# M500X.net
KiCad netlist of a schematic drawn in EAGLE
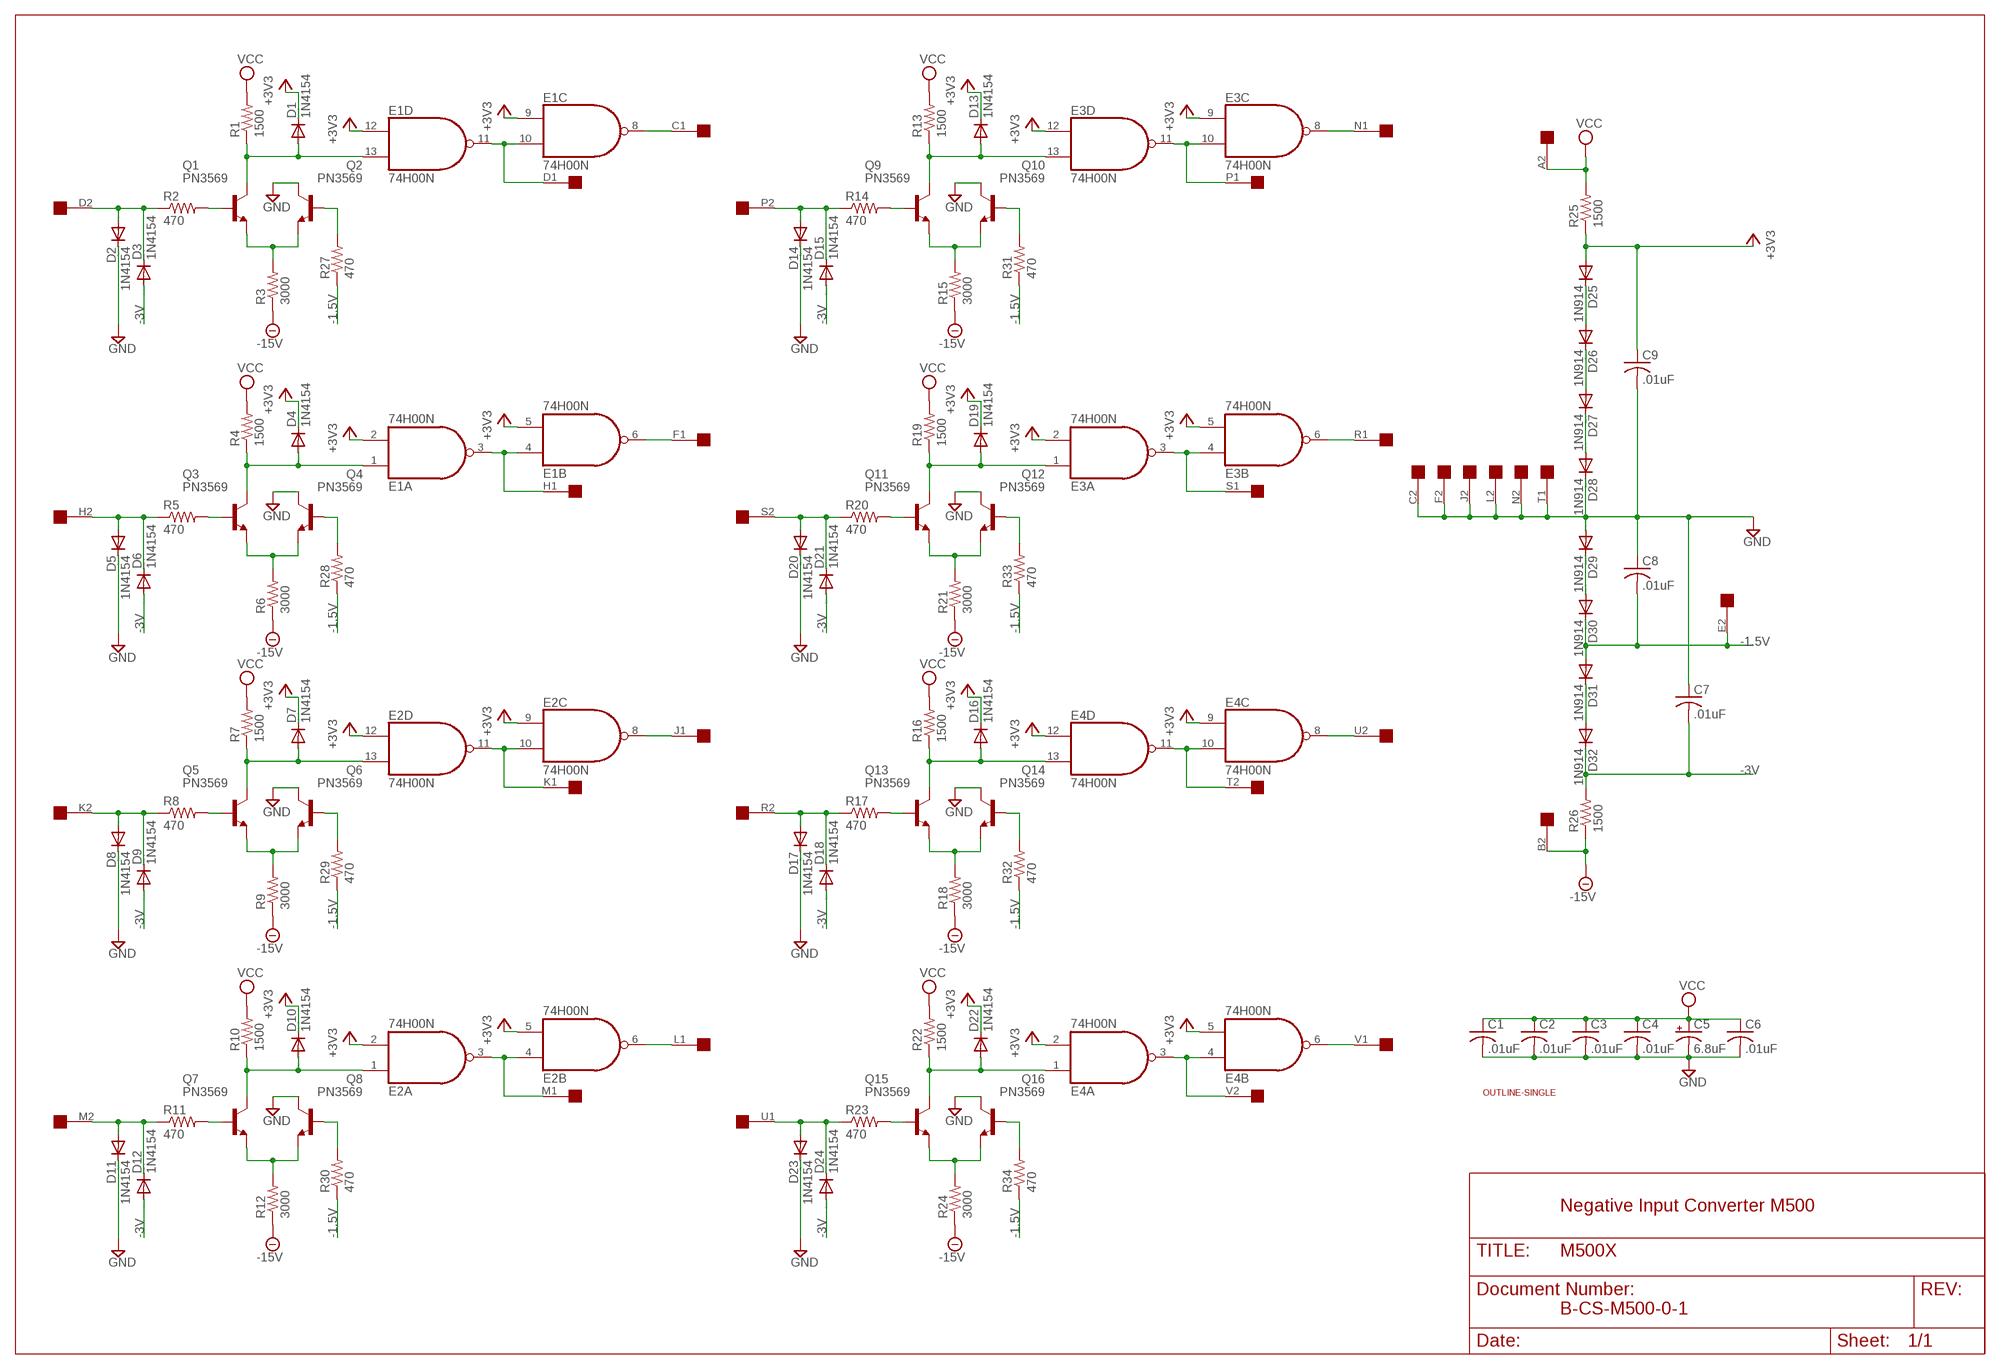
[diagram p0: schematic, sheet 1]

(export (version "E")
  (design (tool "Eeschema 10.0.6"))
  (components
    (comp (ref "C1")
      (value ".01uF")
      (footprint "eagle-import:C050-025X075")
      (libsource (lib "eagle-import") (part "C-US050-025X075"))
    )
    (comp (ref "C2")
      (value ".01uF")
      (footprint "eagle-import:C050-025X075")
      (libsource (lib "eagle-import") (part "C-US050-025X075"))
    )
    (comp (ref "C3")
      (value ".01uF")
      (footprint "eagle-import:C050-025X075")
      (libsource (lib "eagle-import") (part "C-US050-025X075"))
    )
    (comp (ref "C4")
      (value ".01uF")
      (footprint "eagle-import:C050-025X075")
      (libsource (lib "eagle-import") (part "C-US050-025X075"))
    )
    (comp (ref "C5")
      (value "6.8uF")
      (footprint "eagle-import:E12-8")
      (libsource (lib "eagle-import") (part "CPOL-USE20-8AXIAL"))
    )
    (comp (ref "C6")
      (value ".01uF")
      (footprint "eagle-import:C050-025X075")
      (libsource (lib "eagle-import") (part "C-US050-025X075"))
    )
    (comp (ref "C7")
      (value ".01uF")
      (footprint "eagle-import:C050-025X075")
      (libsource (lib "eagle-import") (part "C-US050-025X075"))
    )
    (comp (ref "C8")
      (value ".01uF")
      (footprint "eagle-import:C050-025X075")
      (libsource (lib "eagle-import") (part "C-US050-025X075"))
    )
    (comp (ref "C9")
      (value ".01uF")
      (footprint "eagle-import:C050-025X075")
      (libsource (lib "eagle-import") (part "C-US050-025X075"))
    )
    (comp (ref "D1")
      (value "1N4154")
      (footprint "eagle-import:DO35-10")
      (libsource (lib "eagle-import") (part "1N4148DO35-10"))
    )
    (comp (ref "D2")
      (value "1N4154")
      (footprint "eagle-import:DO35-10")
      (libsource (lib "eagle-import") (part "1N4148DO35-10"))
    )
    (comp (ref "D3")
      (value "1N4154")
      (footprint "eagle-import:DO35-10")
      (libsource (lib "eagle-import") (part "1N4148DO35-10"))
    )
    (comp (ref "D4")
      (value "1N4154")
      (footprint "eagle-import:DO35-10")
      (libsource (lib "eagle-import") (part "1N4148DO35-10"))
    )
    (comp (ref "D5")
      (value "1N4154")
      (footprint "eagle-import:DO35-10")
      (libsource (lib "eagle-import") (part "1N4148DO35-10"))
    )
    (comp (ref "D6")
      (value "1N4154")
      (footprint "eagle-import:DO35-10")
      (libsource (lib "eagle-import") (part "1N4148DO35-10"))
    )
    (comp (ref "D7")
      (value "1N4154")
      (footprint "eagle-import:DO35-10")
      (libsource (lib "eagle-import") (part "1N4148DO35-10"))
    )
    (comp (ref "D8")
      (value "1N4154")
      (footprint "eagle-import:DO35-10")
      (libsource (lib "eagle-import") (part "1N4148DO35-10"))
    )
    (comp (ref "D9")
      (value "1N4154")
      (footprint "eagle-import:DO35-10")
      (libsource (lib "eagle-import") (part "1N4148DO35-10"))
    )
    (comp (ref "D10")
      (value "1N4154")
      (footprint "eagle-import:DO35-10")
      (libsource (lib "eagle-import") (part "1N4148DO35-10"))
    )
    (comp (ref "D11")
      (value "1N4154")
      (footprint "eagle-import:DO35-10")
      (libsource (lib "eagle-import") (part "1N4148DO35-10"))
    )
    (comp (ref "D12")
      (value "1N4154")
      (footprint "eagle-import:DO35-10")
      (libsource (lib "eagle-import") (part "1N4148DO35-10"))
    )
    (comp (ref "D13")
      (value "1N4154")
      (footprint "eagle-import:DO35-10")
      (libsource (lib "eagle-import") (part "1N4148DO35-10"))
    )
    (comp (ref "D14")
      (value "1N4154")
      (footprint "eagle-import:DO35-10")
      (libsource (lib "eagle-import") (part "1N4148DO35-10"))
    )
    (comp (ref "D15")
      (value "1N4154")
      (footprint "eagle-import:DO35-10")
      (libsource (lib "eagle-import") (part "1N4148DO35-10"))
    )
    (comp (ref "D16")
      (value "1N4154")
      (footprint "eagle-import:DO35-10")
      (libsource (lib "eagle-import") (part "1N4148DO35-10"))
    )
    (comp (ref "D17")
      (value "1N4154")
      (footprint "eagle-import:DO35-10")
      (libsource (lib "eagle-import") (part "1N4148DO35-10"))
    )
    (comp (ref "D18")
      (value "1N4154")
      (footprint "eagle-import:DO35-10")
      (libsource (lib "eagle-import") (part "1N4148DO35-10"))
    )
    (comp (ref "D19")
      (value "1N4154")
      (footprint "eagle-import:DO35-10")
      (libsource (lib "eagle-import") (part "1N4148DO35-10"))
    )
    (comp (ref "D20")
      (value "1N4154")
      (footprint "eagle-import:DO35-10")
      (libsource (lib "eagle-import") (part "1N4148DO35-10"))
    )
    (comp (ref "D21")
      (value "1N4154")
      (footprint "eagle-import:DO35-10")
      (libsource (lib "eagle-import") (part "1N4148DO35-10"))
    )
    (comp (ref "D22")
      (value "1N4154")
      (footprint "eagle-import:DO35-10")
      (libsource (lib "eagle-import") (part "1N4148DO35-10"))
    )
    (comp (ref "D23")
      (value "1N4154")
      (footprint "eagle-import:DO35-10")
      (libsource (lib "eagle-import") (part "1N4148DO35-10"))
    )
    (comp (ref "D24")
      (value "1N4154")
      (footprint "eagle-import:DO35-10")
      (libsource (lib "eagle-import") (part "1N4148DO35-10"))
    )
    (comp (ref "D25")
      (value "1N914")
      (footprint "eagle-import:DO35-10")
      (libsource (lib "eagle-import") (part "1N4148DO35-10"))
    )
    (comp (ref "D26")
      (value "1N914")
      (footprint "eagle-import:DO35-10")
      (libsource (lib "eagle-import") (part "1N4148DO35-10"))
    )
    (comp (ref "D27")
      (value "1N914")
      (footprint "eagle-import:DO35-10")
      (libsource (lib "eagle-import") (part "1N4148DO35-10"))
    )
    (comp (ref "D28")
      (value "1N914")
      (footprint "eagle-import:DO35-10")
      (libsource (lib "eagle-import") (part "1N4148DO35-10"))
    )
    (comp (ref "D29")
      (value "1N914")
      (footprint "eagle-import:DO35-10")
      (libsource (lib "eagle-import") (part "1N4148DO35-10"))
    )
    (comp (ref "D30")
      (value "1N914")
      (footprint "eagle-import:DO35-10")
      (libsource (lib "eagle-import") (part "1N4148DO35-10"))
    )
    (comp (ref "D31")
      (value "1N914")
      (footprint "eagle-import:DO35-10")
      (libsource (lib "eagle-import") (part "1N4148DO35-10"))
    )
    (comp (ref "D32")
      (value "1N914")
      (footprint "eagle-import:DO35-10")
      (libsource (lib "eagle-import") (part "1N4148DO35-10"))
    )
    (comp (ref "E1")
      (value "74H00N")
      (footprint "eagle-import:DIL14")
      (libsource (lib "eagle-import") (part "7400N"))
    )
    (comp (ref "E2")
      (value "74H00N")
      (footprint "eagle-import:DIL14")
      (libsource (lib "eagle-import") (part "7400N"))
    )
    (comp (ref "E3")
      (value "74H00N")
      (footprint "eagle-import:DIL14")
      (libsource (lib "eagle-import") (part "7400N"))
    )
    (comp (ref "E4")
      (value "74H00N")
      (footprint "eagle-import:DIL14")
      (libsource (lib "eagle-import") (part "7400N"))
    )
    (comp (ref "Q1")
      (value "PN3569")
      (footprint "eagle-import:TO39")
      (libsource (lib "eagle-import") (part "2N3019"))
    )
    (comp (ref "Q2")
      (value "PN3569")
      (footprint "eagle-import:TO39")
      (libsource (lib "eagle-import") (part "2N3019"))
    )
    (comp (ref "Q3")
      (value "PN3569")
      (footprint "eagle-import:TO39")
      (libsource (lib "eagle-import") (part "2N3019"))
    )
    (comp (ref "Q4")
      (value "PN3569")
      (footprint "eagle-import:TO39")
      (libsource (lib "eagle-import") (part "2N3019"))
    )
    (comp (ref "Q5")
      (value "PN3569")
      (footprint "eagle-import:TO39")
      (libsource (lib "eagle-import") (part "2N3019"))
    )
    (comp (ref "Q6")
      (value "PN3569")
      (footprint "eagle-import:TO39")
      (libsource (lib "eagle-import") (part "2N3019"))
    )
    (comp (ref "Q7")
      (value "PN3569")
      (footprint "eagle-import:TO39")
      (libsource (lib "eagle-import") (part "2N3019"))
    )
    (comp (ref "Q8")
      (value "PN3569")
      (footprint "eagle-import:TO39")
      (libsource (lib "eagle-import") (part "2N3019"))
    )
    (comp (ref "Q9")
      (value "PN3569")
      (footprint "eagle-import:TO39")
      (libsource (lib "eagle-import") (part "2N3019"))
    )
    (comp (ref "Q10")
      (value "PN3569")
      (footprint "eagle-import:TO39")
      (libsource (lib "eagle-import") (part "2N3019"))
    )
    (comp (ref "Q11")
      (value "PN3569")
      (footprint "eagle-import:TO39")
      (libsource (lib "eagle-import") (part "2N3019"))
    )
    (comp (ref "Q12")
      (value "PN3569")
      (footprint "eagle-import:TO39")
      (libsource (lib "eagle-import") (part "2N3019"))
    )
    (comp (ref "Q13")
      (value "PN3569")
      (footprint "eagle-import:TO39")
      (libsource (lib "eagle-import") (part "2N3019"))
    )
    (comp (ref "Q14")
      (value "PN3569")
      (footprint "eagle-import:TO39")
      (libsource (lib "eagle-import") (part "2N3019"))
    )
    (comp (ref "Q15")
      (value "PN3569")
      (footprint "eagle-import:TO39")
      (libsource (lib "eagle-import") (part "2N3019"))
    )
    (comp (ref "Q16")
      (value "PN3569")
      (footprint "eagle-import:TO39")
      (libsource (lib "eagle-import") (part "2N3019"))
    )
    (comp (ref "R1")
      (value "1500")
      (footprint "eagle-import:0207_10")
      (libsource (lib "eagle-import") (part "R-US_0207/10"))
    )
    (comp (ref "R2")
      (value "470")
      (footprint "eagle-import:0207_10")
      (libsource (lib "eagle-import") (part "R-US_0207/10"))
    )
    (comp (ref "R3")
      (value "3000")
      (footprint "eagle-import:0207_10")
      (libsource (lib "eagle-import") (part "R-US_0207/10"))
    )
    (comp (ref "R4")
      (value "1500")
      (footprint "eagle-import:0207_10")
      (libsource (lib "eagle-import") (part "R-US_0207/10"))
    )
    (comp (ref "R5")
      (value "470")
      (footprint "eagle-import:0207_10")
      (libsource (lib "eagle-import") (part "R-US_0207/10"))
    )
    (comp (ref "R6")
      (value "3000")
      (footprint "eagle-import:0207_10")
      (libsource (lib "eagle-import") (part "R-US_0207/10"))
    )
    (comp (ref "R7")
      (value "1500")
      (footprint "eagle-import:0207_10")
      (libsource (lib "eagle-import") (part "R-US_0207/10"))
    )
    (comp (ref "R8")
      (value "470")
      (footprint "eagle-import:0207_10")
      (libsource (lib "eagle-import") (part "R-US_0207/10"))
    )
    (comp (ref "R9")
      (value "3000")
      (footprint "eagle-import:0207_10")
      (libsource (lib "eagle-import") (part "R-US_0207/10"))
    )
    (comp (ref "R10")
      (value "1500")
      (footprint "eagle-import:0207_10")
      (libsource (lib "eagle-import") (part "R-US_0207/10"))
    )
    (comp (ref "R11")
      (value "470")
      (footprint "eagle-import:0207_10")
      (libsource (lib "eagle-import") (part "R-US_0207/10"))
    )
    (comp (ref "R12")
      (value "3000")
      (footprint "eagle-import:0207_10")
      (libsource (lib "eagle-import") (part "R-US_0207/10"))
    )
    (comp (ref "R13")
      (value "1500")
      (footprint "eagle-import:0207_10")
      (libsource (lib "eagle-import") (part "R-US_0207/10"))
    )
    (comp (ref "R14")
      (value "470")
      (footprint "eagle-import:0207_10")
      (libsource (lib "eagle-import") (part "R-US_0207/10"))
    )
    (comp (ref "R15")
      (value "3000")
      (footprint "eagle-import:0207_10")
      (libsource (lib "eagle-import") (part "R-US_0207/10"))
    )
    (comp (ref "R16")
      (value "1500")
      (footprint "eagle-import:0207_10")
      (libsource (lib "eagle-import") (part "R-US_0207/10"))
    )
    (comp (ref "R17")
      (value "470")
      (footprint "eagle-import:0207_10")
      (libsource (lib "eagle-import") (part "R-US_0207/10"))
    )
    (comp (ref "R18")
      (value "3000")
      (footprint "eagle-import:0207_10")
      (libsource (lib "eagle-import") (part "R-US_0207/10"))
    )
    (comp (ref "R19")
      (value "1500")
      (footprint "eagle-import:0207_10")
      (libsource (lib "eagle-import") (part "R-US_0207/10"))
    )
    (comp (ref "R20")
      (value "470")
      (footprint "eagle-import:0207_10")
      (libsource (lib "eagle-import") (part "R-US_0207/10"))
    )
    (comp (ref "R21")
      (value "3000")
      (footprint "eagle-import:0207_10")
      (libsource (lib "eagle-import") (part "R-US_0207/10"))
    )
    (comp (ref "R22")
      (value "1500")
      (footprint "eagle-import:0207_10")
      (libsource (lib "eagle-import") (part "R-US_0207/10"))
    )
    (comp (ref "R23")
      (value "470")
      (footprint "eagle-import:0207_10")
      (libsource (lib "eagle-import") (part "R-US_0207/10"))
    )
    (comp (ref "R24")
      (value "3000")
      (footprint "eagle-import:0207_10")
      (libsource (lib "eagle-import") (part "R-US_0207/10"))
    )
    (comp (ref "R25")
      (value "1500")
      (footprint "eagle-import:0207_10")
      (libsource (lib "eagle-import") (part "R-US_0207/10"))
    )
    (comp (ref "R26")
      (value "1500")
      (footprint "eagle-import:0207_10")
      (libsource (lib "eagle-import") (part "R-US_0207/10"))
    )
    (comp (ref "R27")
      (value "470")
      (footprint "eagle-import:0207_10")
      (libsource (lib "eagle-import") (part "R-US_0207/10"))
    )
    (comp (ref "R28")
      (value "470")
      (footprint "eagle-import:0207_10")
      (libsource (lib "eagle-import") (part "R-US_0207/10"))
    )
    (comp (ref "R29")
      (value "470")
      (footprint "eagle-import:0207_10")
      (libsource (lib "eagle-import") (part "R-US_0207/10"))
    )
    (comp (ref "R30")
      (value "470")
      (footprint "eagle-import:0207_10")
      (libsource (lib "eagle-import") (part "R-US_0207/10"))
    )
    (comp (ref "R31")
      (value "470")
      (footprint "eagle-import:0207_10")
      (libsource (lib "eagle-import") (part "R-US_0207/10"))
    )
    (comp (ref "R32")
      (value "470")
      (footprint "eagle-import:0207_10")
      (libsource (lib "eagle-import") (part "R-US_0207/10"))
    )
    (comp (ref "R33")
      (value "470")
      (footprint "eagle-import:0207_10")
      (libsource (lib "eagle-import") (part "R-US_0207/10"))
    )
    (comp (ref "R34")
      (value "470")
      (footprint "eagle-import:0207_10")
      (libsource (lib "eagle-import") (part "R-US_0207/10"))
    )
    (comp (ref "U$1")
      (value "OUTLINE-SINGLE")
      (footprint "eagle-import:SINGLE")
      (libsource (lib "eagle-import") (part "OUTLINE-SINGLE"))
    )
    (comp (ref "U$3")
      (value "SINGLE")
      (footprint "eagle-import:EDGE-CON2")
      (libsource (lib "eagle-import") (part "SINGLE"))
    )
  )
  (nets
    (net (code "1") (name "+3V3") (class "Default")
      (node (ref "C9") (pin "1") (pinfunction "1_1") (pintype "passive"))
      (node (ref "D1") (pin "C") (pinfunction "C_C") (pintype "passive"))
      (node (ref "D10") (pin "C") (pinfunction "C_C") (pintype "passive"))
      (node (ref "D13") (pin "C") (pinfunction "C_C") (pintype "passive"))
      (node (ref "D16") (pin "C") (pinfunction "C_C") (pintype "passive"))
      (node (ref "D19") (pin "C") (pinfunction "C_C") (pintype "passive"))
      (node (ref "D22") (pin "C") (pinfunction "C_C") (pintype "passive"))
      (node (ref "D25") (pin "A") (pinfunction "A_A") (pintype "passive"))
      (node (ref "D4") (pin "C") (pinfunction "C_C") (pintype "passive"))
      (node (ref "D7") (pin "C") (pinfunction "C_C") (pintype "passive"))
      (node (ref "E1") (pin "12") (pinfunction "I0_12") (pintype "input"))
      (node (ref "E1") (pin "2") (pinfunction "I1_2") (pintype "input"))
      (node (ref "E1") (pin "5") (pinfunction "I1_5") (pintype "input"))
      (node (ref "E1") (pin "9") (pinfunction "I0_9") (pintype "input"))
      (node (ref "E2") (pin "12") (pinfunction "I0_12") (pintype "input"))
      (node (ref "E2") (pin "2") (pinfunction "I1_2") (pintype "input"))
      (node (ref "E2") (pin "5") (pinfunction "I1_5") (pintype "input"))
      (node (ref "E2") (pin "9") (pinfunction "I0_9") (pintype "input"))
      (node (ref "E3") (pin "12") (pinfunction "I0_12") (pintype "input"))
      (node (ref "E3") (pin "2") (pinfunction "I1_2") (pintype "input"))
      (node (ref "E3") (pin "5") (pinfunction "I1_5") (pintype "input"))
      (node (ref "E3") (pin "9") (pinfunction "I0_9") (pintype "input"))
      (node (ref "E4") (pin "12") (pinfunction "I0_12") (pintype "input"))
      (node (ref "E4") (pin "2") (pinfunction "I1_2") (pintype "input"))
      (node (ref "E4") (pin "5") (pinfunction "I1_5") (pintype "input"))
      (node (ref "E4") (pin "9") (pinfunction "I0_9") (pintype "input"))
      (node (ref "R25") (pin "1") (pinfunction "1_1") (pintype "passive"))
    )
    (net (code "2") (name "-15V") (class "Default")
      (node (ref "R12") (pin "1") (pinfunction "1_1") (pintype "passive"))
      (node (ref "R15") (pin "1") (pinfunction "1_1") (pintype "passive"))
      (node (ref "R18") (pin "1") (pinfunction "1_1") (pintype "passive"))
      (node (ref "R21") (pin "1") (pinfunction "1_1") (pintype "passive"))
      (node (ref "R24") (pin "1") (pinfunction "1_1") (pintype "passive"))
      (node (ref "R26") (pin "1") (pinfunction "1_1") (pintype "passive"))
      (node (ref "R3") (pin "1") (pinfunction "1_1") (pintype "passive"))
      (node (ref "R6") (pin "1") (pinfunction "1_1") (pintype "passive"))
      (node (ref "R9") (pin "1") (pinfunction "1_1") (pintype "passive"))
      (node (ref "U$3") (pin "B2") (pinfunction "1_B2") (pintype "bidirectional"))
    )
    (net (code "3") (name "/-1.5V") (class "Default")
      (node (ref "C8") (pin "2") (pinfunction "2_2") (pintype "passive"))
      (node (ref "D30") (pin "C") (pinfunction "C_C") (pintype "passive"))
      (node (ref "D31") (pin "A") (pinfunction "A_A") (pintype "passive"))
      (node (ref "R27") (pin "1") (pinfunction "1_1") (pintype "passive"))
      (node (ref "R28") (pin "1") (pinfunction "1_1") (pintype "passive"))
      (node (ref "R29") (pin "1") (pinfunction "1_1") (pintype "passive"))
      (node (ref "R30") (pin "1") (pinfunction "1_1") (pintype "passive"))
      (node (ref "R31") (pin "1") (pinfunction "1_1") (pintype "passive"))
      (node (ref "R32") (pin "1") (pinfunction "1_1") (pintype "passive"))
      (node (ref "R33") (pin "1") (pinfunction "1_1") (pintype "passive"))
      (node (ref "R34") (pin "1") (pinfunction "1_1") (pintype "passive"))
      (node (ref "U$3") (pin "E2") (pinfunction "1_E2") (pintype "bidirectional"))
    )
    (net (code "4") (name "/-3V") (class "Default")
      (node (ref "C7") (pin "2") (pinfunction "2_2") (pintype "passive"))
      (node (ref "D12") (pin "A") (pinfunction "A_A") (pintype "passive"))
      (node (ref "D15") (pin "A") (pinfunction "A_A") (pintype "passive"))
      (node (ref "D18") (pin "A") (pinfunction "A_A") (pintype "passive"))
      (node (ref "D21") (pin "A") (pinfunction "A_A") (pintype "passive"))
      (node (ref "D24") (pin "A") (pinfunction "A_A") (pintype "passive"))
      (node (ref "D3") (pin "A") (pinfunction "A_A") (pintype "passive"))
      (node (ref "D32") (pin "C") (pinfunction "C_C") (pintype "passive"))
      (node (ref "D6") (pin "A") (pinfunction "A_A") (pintype "passive"))
      (node (ref "D9") (pin "A") (pinfunction "A_A") (pintype "passive"))
      (node (ref "R26") (pin "2") (pinfunction "2_2") (pintype "passive"))
    )
    (net (code "5") (name "GND") (class "Default")
      (node (ref "C1") (pin "2") (pinfunction "2_2") (pintype "passive"))
      (node (ref "C2") (pin "2") (pinfunction "2_2") (pintype "passive"))
      (node (ref "C3") (pin "2") (pinfunction "2_2") (pintype "passive"))
      (node (ref "C4") (pin "2") (pinfunction "2_2") (pintype "passive"))
      (node (ref "C5") (pin "-") (pinfunction "-_-") (pintype "passive"))
      (node (ref "C6") (pin "2") (pinfunction "2_2") (pintype "passive"))
      (node (ref "C7") (pin "1") (pinfunction "1_1") (pintype "passive"))
      (node (ref "C8") (pin "1") (pinfunction "1_1") (pintype "passive"))
      (node (ref "C9") (pin "2") (pinfunction "2_2") (pintype "passive"))
      (node (ref "D11") (pin "C") (pinfunction "C_C") (pintype "passive"))
      (node (ref "D14") (pin "C") (pinfunction "C_C") (pintype "passive"))
      (node (ref "D17") (pin "C") (pinfunction "C_C") (pintype "passive"))
      (node (ref "D2") (pin "C") (pinfunction "C_C") (pintype "passive"))
      (node (ref "D20") (pin "C") (pinfunction "C_C") (pintype "passive"))
      (node (ref "D23") (pin "C") (pinfunction "C_C") (pintype "passive"))
      (node (ref "D28") (pin "C") (pinfunction "C_C") (pintype "passive"))
      (node (ref "D29") (pin "A") (pinfunction "A_A") (pintype "passive"))
      (node (ref "D5") (pin "C") (pinfunction "C_C") (pintype "passive"))
      (node (ref "D8") (pin "C") (pinfunction "C_C") (pintype "passive"))
      (node (ref "Q10") (pin "3") (pinfunction "C_3") (pintype "passive"))
      (node (ref "Q12") (pin "3") (pinfunction "C_3") (pintype "passive"))
      (node (ref "Q14") (pin "3") (pinfunction "C_3") (pintype "passive"))
      (node (ref "Q16") (pin "3") (pinfunction "C_3") (pintype "passive"))
      (node (ref "Q2") (pin "3") (pinfunction "C_3") (pintype "passive"))
      (node (ref "Q4") (pin "3") (pinfunction "C_3") (pintype "passive"))
      (node (ref "Q6") (pin "3") (pinfunction "C_3") (pintype "passive"))
      (node (ref "Q8") (pin "3") (pinfunction "C_3") (pintype "passive"))
      (node (ref "U$3") (pin "C2") (pinfunction "1_C2") (pintype "bidirectional"))
      (node (ref "U$3") (pin "F2") (pinfunction "1_F2") (pintype "bidirectional"))
      (node (ref "U$3") (pin "J2") (pinfunction "1_J2") (pintype "bidirectional"))
      (node (ref "U$3") (pin "L2") (pinfunction "1_L2") (pintype "bidirectional"))
      (node (ref "U$3") (pin "N2") (pinfunction "1_N2") (pintype "bidirectional"))
      (node (ref "U$3") (pin "T1") (pinfunction "1_T1") (pintype "bidirectional"))
    )
    (net (code "6") (name "Net-(D25-PadC)") (class "Default")
      (node (ref "D25") (pin "C") (pinfunction "C_C") (pintype "passive"))
      (node (ref "D26") (pin "A") (pinfunction "A_A") (pintype "passive"))
    )
    (net (code "7") (name "Net-(D26-PadC)") (class "Default")
      (node (ref "D26") (pin "C") (pinfunction "C_C") (pintype "passive"))
      (node (ref "D27") (pin "A") (pinfunction "A_A") (pintype "passive"))
    )
    (net (code "8") (name "Net-(D27-PadC)") (class "Default")
      (node (ref "D27") (pin "C") (pinfunction "C_C") (pintype "passive"))
      (node (ref "D28") (pin "A") (pinfunction "A_A") (pintype "passive"))
    )
    (net (code "9") (name "Net-(D29-PadC)") (class "Default")
      (node (ref "D29") (pin "C") (pinfunction "C_C") (pintype "passive"))
      (node (ref "D30") (pin "A") (pinfunction "A_A") (pintype "passive"))
    )
    (net (code "10") (name "Net-(D31-PadC)") (class "Default")
      (node (ref "D31") (pin "C") (pinfunction "C_C") (pintype "passive"))
      (node (ref "D32") (pin "A") (pinfunction "A_A") (pintype "passive"))
    )
    (net (code "11") (name "Net-(E1A-I0)") (class "Default")
      (node (ref "D4") (pin "A") (pinfunction "A_A") (pintype "passive"))
      (node (ref "E1") (pin "1") (pinfunction "I0_1") (pintype "input"))
      (node (ref "Q3") (pin "3") (pinfunction "C_3") (pintype "passive"))
      (node (ref "R4") (pin "1") (pinfunction "1_1") (pintype "passive"))
    )
    (net (code "12") (name "Net-(E1A-O)") (class "Default")
      (node (ref "E1") (pin "3") (pinfunction "O_3") (pintype "output"))
      (node (ref "E1") (pin "4") (pinfunction "I0_4") (pintype "input"))
      (node (ref "U$3") (pin "H1") (pinfunction "1_H1") (pintype "bidirectional"))
    )
    (net (code "13") (name "Net-(E1B-O)") (class "Default")
      (node (ref "E1") (pin "6") (pinfunction "O_6") (pintype "output"))
      (node (ref "U$3") (pin "F1") (pinfunction "1_F1") (pintype "bidirectional"))
    )
    (net (code "14") (name "Net-(E1C-I1)") (class "Default")
      (node (ref "E1") (pin "10") (pinfunction "I1_10") (pintype "input"))
      (node (ref "E1") (pin "11") (pinfunction "O_11") (pintype "output"))
      (node (ref "U$3") (pin "D1") (pinfunction "1_D1") (pintype "bidirectional"))
    )
    (net (code "15") (name "Net-(E1C-O)") (class "Default")
      (node (ref "E1") (pin "8") (pinfunction "O_8") (pintype "output"))
      (node (ref "U$3") (pin "C1") (pinfunction "1_C1") (pintype "bidirectional"))
    )
    (net (code "16") (name "Net-(E1D-I1)") (class "Default")
      (node (ref "D1") (pin "A") (pinfunction "A_A") (pintype "passive"))
      (node (ref "E1") (pin "13") (pinfunction "I1_13") (pintype "input"))
      (node (ref "Q1") (pin "3") (pinfunction "C_3") (pintype "passive"))
      (node (ref "R1") (pin "1") (pinfunction "1_1") (pintype "passive"))
    )
    (net (code "17") (name "Net-(E2A-I0)") (class "Default")
      (node (ref "D10") (pin "A") (pinfunction "A_A") (pintype "passive"))
      (node (ref "E2") (pin "1") (pinfunction "I0_1") (pintype "input"))
      (node (ref "Q7") (pin "3") (pinfunction "C_3") (pintype "passive"))
      (node (ref "R10") (pin "1") (pinfunction "1_1") (pintype "passive"))
    )
    (net (code "18") (name "Net-(E2A-O)") (class "Default")
      (node (ref "E2") (pin "3") (pinfunction "O_3") (pintype "output"))
      (node (ref "E2") (pin "4") (pinfunction "I0_4") (pintype "input"))
      (node (ref "U$3") (pin "M1") (pinfunction "1_M1") (pintype "bidirectional"))
    )
    (net (code "19") (name "Net-(E2B-O)") (class "Default")
      (node (ref "E2") (pin "6") (pinfunction "O_6") (pintype "output"))
      (node (ref "U$3") (pin "L1") (pinfunction "1_L1") (pintype "bidirectional"))
    )
    (net (code "20") (name "Net-(E2C-I1)") (class "Default")
      (node (ref "E2") (pin "10") (pinfunction "I1_10") (pintype "input"))
      (node (ref "E2") (pin "11") (pinfunction "O_11") (pintype "output"))
      (node (ref "U$3") (pin "K1") (pinfunction "1_K1") (pintype "bidirectional"))
    )
    (net (code "21") (name "Net-(E2C-O)") (class "Default")
      (node (ref "E2") (pin "8") (pinfunction "O_8") (pintype "output"))
      (node (ref "U$3") (pin "J1") (pinfunction "1_J1") (pintype "bidirectional"))
    )
    (net (code "22") (name "Net-(E2D-I1)") (class "Default")
      (node (ref "D7") (pin "A") (pinfunction "A_A") (pintype "passive"))
      (node (ref "E2") (pin "13") (pinfunction "I1_13") (pintype "input"))
      (node (ref "Q5") (pin "3") (pinfunction "C_3") (pintype "passive"))
      (node (ref "R7") (pin "1") (pinfunction "1_1") (pintype "passive"))
    )
    (net (code "23") (name "Net-(E3A-I0)") (class "Default")
      (node (ref "D19") (pin "A") (pinfunction "A_A") (pintype "passive"))
      (node (ref "E3") (pin "1") (pinfunction "I0_1") (pintype "input"))
      (node (ref "Q11") (pin "3") (pinfunction "C_3") (pintype "passive"))
      (node (ref "R19") (pin "1") (pinfunction "1_1") (pintype "passive"))
    )
    (net (code "24") (name "Net-(E3A-O)") (class "Default")
      (node (ref "E3") (pin "3") (pinfunction "O_3") (pintype "output"))
      (node (ref "E3") (pin "4") (pinfunction "I0_4") (pintype "input"))
      (node (ref "U$3") (pin "S1") (pinfunction "1_S1") (pintype "bidirectional"))
    )
    (net (code "25") (name "Net-(E3B-O)") (class "Default")
      (node (ref "E3") (pin "6") (pinfunction "O_6") (pintype "output"))
      (node (ref "U$3") (pin "R1") (pinfunction "1_R1") (pintype "bidirectional"))
    )
    (net (code "26") (name "Net-(E3C-I1)") (class "Default")
      (node (ref "E3") (pin "10") (pinfunction "I1_10") (pintype "input"))
      (node (ref "E3") (pin "11") (pinfunction "O_11") (pintype "output"))
      (node (ref "U$3") (pin "P1") (pinfunction "1_P1") (pintype "bidirectional"))
    )
    (net (code "27") (name "Net-(E3C-O)") (class "Default")
      (node (ref "E3") (pin "8") (pinfunction "O_8") (pintype "output"))
      (node (ref "U$3") (pin "N1") (pinfunction "1_N1") (pintype "bidirectional"))
    )
    (net (code "28") (name "Net-(E3D-I1)") (class "Default")
      (node (ref "D13") (pin "A") (pinfunction "A_A") (pintype "passive"))
      (node (ref "E3") (pin "13") (pinfunction "I1_13") (pintype "input"))
      (node (ref "Q9") (pin "3") (pinfunction "C_3") (pintype "passive"))
      (node (ref "R13") (pin "1") (pinfunction "1_1") (pintype "passive"))
    )
    (net (code "29") (name "Net-(E4A-I0)") (class "Default")
      (node (ref "D22") (pin "A") (pinfunction "A_A") (pintype "passive"))
      (node (ref "E4") (pin "1") (pinfunction "I0_1") (pintype "input"))
      (node (ref "Q15") (pin "3") (pinfunction "C_3") (pintype "passive"))
      (node (ref "R22") (pin "1") (pinfunction "1_1") (pintype "passive"))
    )
    (net (code "30") (name "Net-(E4A-O)") (class "Default")
      (node (ref "E4") (pin "3") (pinfunction "O_3") (pintype "output"))
      (node (ref "E4") (pin "4") (pinfunction "I0_4") (pintype "input"))
      (node (ref "U$3") (pin "V2") (pinfunction "1_V2") (pintype "bidirectional"))
    )
    (net (code "31") (name "Net-(E4B-O)") (class "Default")
      (node (ref "E4") (pin "6") (pinfunction "O_6") (pintype "output"))
      (node (ref "U$3") (pin "V1") (pinfunction "1_V1") (pintype "bidirectional"))
    )
    (net (code "32") (name "Net-(E4C-I1)") (class "Default")
      (node (ref "E4") (pin "10") (pinfunction "I1_10") (pintype "input"))
      (node (ref "E4") (pin "11") (pinfunction "O_11") (pintype "output"))
      (node (ref "U$3") (pin "T2") (pinfunction "1_T2") (pintype "bidirectional"))
    )
    (net (code "33") (name "Net-(E4C-O)") (class "Default")
      (node (ref "E4") (pin "8") (pinfunction "O_8") (pintype "output"))
      (node (ref "U$3") (pin "U2") (pinfunction "1_U2") (pintype "bidirectional"))
    )
    (net (code "34") (name "Net-(E4D-I1)") (class "Default")
      (node (ref "D16") (pin "A") (pinfunction "A_A") (pintype "passive"))
      (node (ref "E4") (pin "13") (pinfunction "I1_13") (pintype "input"))
      (node (ref "Q13") (pin "3") (pinfunction "C_3") (pintype "passive"))
      (node (ref "R16") (pin "1") (pinfunction "1_1") (pintype "passive"))
    )
    (net (code "35") (name "Net-(Q1-B)") (class "Default")
      (node (ref "Q1") (pin "2") (pinfunction "B_2") (pintype "passive"))
      (node (ref "R2") (pin "2") (pinfunction "2_2") (pintype "passive"))
    )
    (net (code "36") (name "Net-(Q1-E)") (class "Default")
      (node (ref "Q1") (pin "1") (pinfunction "E_1") (pintype "passive"))
      (node (ref "Q2") (pin "1") (pinfunction "E_1") (pintype "passive"))
      (node (ref "R3") (pin "2") (pinfunction "2_2") (pintype "passive"))
    )
    (net (code "37") (name "Net-(Q2-B)") (class "Default")
      (node (ref "Q2") (pin "2") (pinfunction "B_2") (pintype "passive"))
      (node (ref "R27") (pin "2") (pinfunction "2_2") (pintype "passive"))
    )
    (net (code "38") (name "Net-(Q3-B)") (class "Default")
      (node (ref "Q3") (pin "2") (pinfunction "B_2") (pintype "passive"))
      (node (ref "R5") (pin "2") (pinfunction "2_2") (pintype "passive"))
    )
    (net (code "39") (name "Net-(Q3-E)") (class "Default")
      (node (ref "Q3") (pin "1") (pinfunction "E_1") (pintype "passive"))
      (node (ref "Q4") (pin "1") (pinfunction "E_1") (pintype "passive"))
      (node (ref "R6") (pin "2") (pinfunction "2_2") (pintype "passive"))
    )
    (net (code "40") (name "Net-(Q4-B)") (class "Default")
      (node (ref "Q4") (pin "2") (pinfunction "B_2") (pintype "passive"))
      (node (ref "R28") (pin "2") (pinfunction "2_2") (pintype "passive"))
    )
    (net (code "41") (name "Net-(Q5-B)") (class "Default")
      (node (ref "Q5") (pin "2") (pinfunction "B_2") (pintype "passive"))
      (node (ref "R8") (pin "2") (pinfunction "2_2") (pintype "passive"))
    )
    (net (code "42") (name "Net-(Q5-E)") (class "Default")
      (node (ref "Q5") (pin "1") (pinfunction "E_1") (pintype "passive"))
      (node (ref "Q6") (pin "1") (pinfunction "E_1") (pintype "passive"))
      (node (ref "R9") (pin "2") (pinfunction "2_2") (pintype "passive"))
    )
    (net (code "43") (name "Net-(Q6-B)") (class "Default")
      (node (ref "Q6") (pin "2") (pinfunction "B_2") (pintype "passive"))
      (node (ref "R29") (pin "2") (pinfunction "2_2") (pintype "passive"))
    )
    (net (code "44") (name "Net-(Q7-B)") (class "Default")
      (node (ref "Q7") (pin "2") (pinfunction "B_2") (pintype "passive"))
      (node (ref "R11") (pin "2") (pinfunction "2_2") (pintype "passive"))
    )
    (net (code "45") (name "Net-(Q7-E)") (class "Default")
      (node (ref "Q7") (pin "1") (pinfunction "E_1") (pintype "passive"))
      (node (ref "Q8") (pin "1") (pinfunction "E_1") (pintype "passive"))
      (node (ref "R12") (pin "2") (pinfunction "2_2") (pintype "passive"))
    )
    (net (code "46") (name "Net-(Q8-B)") (class "Default")
      (node (ref "Q8") (pin "2") (pinfunction "B_2") (pintype "passive"))
      (node (ref "R30") (pin "2") (pinfunction "2_2") (pintype "passive"))
    )
    (net (code "47") (name "Net-(Q9-B)") (class "Default")
      (node (ref "Q9") (pin "2") (pinfunction "B_2") (pintype "passive"))
      (node (ref "R14") (pin "2") (pinfunction "2_2") (pintype "passive"))
    )
    (net (code "48") (name "Net-(Q10-B)") (class "Default")
      (node (ref "Q10") (pin "2") (pinfunction "B_2") (pintype "passive"))
      (node (ref "R31") (pin "2") (pinfunction "2_2") (pintype "passive"))
    )
    (net (code "49") (name "Net-(Q10-E)") (class "Default")
      (node (ref "Q10") (pin "1") (pinfunction "E_1") (pintype "passive"))
      (node (ref "Q9") (pin "1") (pinfunction "E_1") (pintype "passive"))
      (node (ref "R15") (pin "2") (pinfunction "2_2") (pintype "passive"))
    )
    (net (code "50") (name "Net-(Q11-B)") (class "Default")
      (node (ref "Q11") (pin "2") (pinfunction "B_2") (pintype "passive"))
      (node (ref "R20") (pin "2") (pinfunction "2_2") (pintype "passive"))
    )
    (net (code "51") (name "Net-(Q11-E)") (class "Default")
      (node (ref "Q11") (pin "1") (pinfunction "E_1") (pintype "passive"))
      (node (ref "Q12") (pin "1") (pinfunction "E_1") (pintype "passive"))
      (node (ref "R21") (pin "2") (pinfunction "2_2") (pintype "passive"))
    )
    (net (code "52") (name "Net-(Q12-B)") (class "Default")
      (node (ref "Q12") (pin "2") (pinfunction "B_2") (pintype "passive"))
      (node (ref "R33") (pin "2") (pinfunction "2_2") (pintype "passive"))
    )
    (net (code "53") (name "Net-(Q13-B)") (class "Default")
      (node (ref "Q13") (pin "2") (pinfunction "B_2") (pintype "passive"))
      (node (ref "R17") (pin "2") (pinfunction "2_2") (pintype "passive"))
    )
    (net (code "54") (name "Net-(Q13-E)") (class "Default")
      (node (ref "Q13") (pin "1") (pinfunction "E_1") (pintype "passive"))
      (node (ref "Q14") (pin "1") (pinfunction "E_1") (pintype "passive"))
      (node (ref "R18") (pin "2") (pinfunction "2_2") (pintype "passive"))
    )
    (net (code "55") (name "Net-(Q14-B)") (class "Default")
      (node (ref "Q14") (pin "2") (pinfunction "B_2") (pintype "passive"))
      (node (ref "R32") (pin "2") (pinfunction "2_2") (pintype "passive"))
    )
    (net (code "56") (name "Net-(Q15-B)") (class "Default")
      (node (ref "Q15") (pin "2") (pinfunction "B_2") (pintype "passive"))
      (node (ref "R23") (pin "2") (pinfunction "2_2") (pintype "passive"))
    )
    (net (code "57") (name "Net-(Q15-E)") (class "Default")
      (node (ref "Q15") (pin "1") (pinfunction "E_1") (pintype "passive"))
      (node (ref "Q16") (pin "1") (pinfunction "E_1") (pintype "passive"))
      (node (ref "R24") (pin "2") (pinfunction "2_2") (pintype "passive"))
    )
    (net (code "58") (name "Net-(Q16-B)") (class "Default")
      (node (ref "Q16") (pin "2") (pinfunction "B_2") (pintype "passive"))
      (node (ref "R34") (pin "2") (pinfunction "2_2") (pintype "passive"))
    )
    (net (code "59") (name "Net-(U$3AB-1)") (class "Default")
      (node (ref "D17") (pin "A") (pinfunction "A_A") (pintype "passive"))
      (node (ref "D18") (pin "C") (pinfunction "C_C") (pintype "passive"))
      (node (ref "R17") (pin "1") (pinfunction "1_1") (pintype "passive"))
      (node (ref "U$3") (pin "R2") (pinfunction "1_R2") (pintype "bidirectional"))
    )
    (net (code "60") (name "Net-(U$3AD-1)") (class "Default")
      (node (ref "D20") (pin "A") (pinfunction "A_A") (pintype "passive"))
      (node (ref "D21") (pin "C") (pinfunction "C_C") (pintype "passive"))
      (node (ref "R20") (pin "1") (pinfunction "1_1") (pintype "passive"))
      (node (ref "U$3") (pin "S2") (pinfunction "1_S2") (pintype "bidirectional"))
    )
    (net (code "61") (name "Net-(U$3AG-1)") (class "Default")
      (node (ref "D23") (pin "A") (pinfunction "A_A") (pintype "passive"))
      (node (ref "D24") (pin "C") (pinfunction "C_C") (pintype "passive"))
      (node (ref "R23") (pin "1") (pinfunction "1_1") (pintype "passive"))
      (node (ref "U$3") (pin "U1") (pinfunction "1_U1") (pintype "bidirectional"))
    )
    (net (code "62") (name "Net-(U$3H-1)") (class "Default")
      (node (ref "D2") (pin "A") (pinfunction "A_A") (pintype "passive"))
      (node (ref "D3") (pin "C") (pinfunction "C_C") (pintype "passive"))
      (node (ref "R2") (pin "1") (pinfunction "1_1") (pintype "passive"))
      (node (ref "U$3") (pin "D2") (pinfunction "1_D2") (pintype "bidirectional"))
    )
    (net (code "63") (name "Net-(U$3N-1)") (class "Default")
      (node (ref "D5") (pin "A") (pinfunction "A_A") (pintype "passive"))
      (node (ref "D6") (pin "C") (pinfunction "C_C") (pintype "passive"))
      (node (ref "R5") (pin "1") (pinfunction "1_1") (pintype "passive"))
      (node (ref "U$3") (pin "H2") (pinfunction "1_H2") (pintype "bidirectional"))
    )
    (net (code "64") (name "Net-(U$3R-1)") (class "Default")
      (node (ref "D8") (pin "A") (pinfunction "A_A") (pintype "passive"))
      (node (ref "D9") (pin "C") (pinfunction "C_C") (pintype "passive"))
      (node (ref "R8") (pin "1") (pinfunction "1_1") (pintype "passive"))
      (node (ref "U$3") (pin "K2") (pinfunction "1_K2") (pintype "bidirectional"))
    )
    (net (code "65") (name "Net-(U$3V-1)") (class "Default")
      (node (ref "D11") (pin "A") (pinfunction "A_A") (pintype "passive"))
      (node (ref "D12") (pin "C") (pinfunction "C_C") (pintype "passive"))
      (node (ref "R11") (pin "1") (pinfunction "1_1") (pintype "passive"))
      (node (ref "U$3") (pin "M2") (pinfunction "1_M2") (pintype "bidirectional"))
    )
    (net (code "66") (name "Net-(U$3Z-1)") (class "Default")
      (node (ref "D14") (pin "A") (pinfunction "A_A") (pintype "passive"))
      (node (ref "D15") (pin "C") (pinfunction "C_C") (pintype "passive"))
      (node (ref "R14") (pin "1") (pinfunction "1_1") (pintype "passive"))
      (node (ref "U$3") (pin "P2") (pinfunction "1_P2") (pintype "bidirectional"))
    )
    (net (code "67") (name "VCC") (class "Default")
      (node (ref "C1") (pin "1") (pinfunction "1_1") (pintype "passive"))
      (node (ref "C2") (pin "1") (pinfunction "1_1") (pintype "passive"))
      (node (ref "C3") (pin "1") (pinfunction "1_1") (pintype "passive"))
      (node (ref "C4") (pin "1") (pinfunction "1_1") (pintype "passive"))
      (node (ref "C5") (pin "+") (pinfunction "+_+") (pintype "passive"))
      (node (ref "C6") (pin "1") (pinfunction "1_1") (pintype "passive"))
      (node (ref "R1") (pin "2") (pinfunction "2_2") (pintype "passive"))
      (node (ref "R10") (pin "2") (pinfunction "2_2") (pintype "passive"))
      (node (ref "R13") (pin "2") (pinfunction "2_2") (pintype "passive"))
      (node (ref "R16") (pin "2") (pinfunction "2_2") (pintype "passive"))
      (node (ref "R19") (pin "2") (pinfunction "2_2") (pintype "passive"))
      (node (ref "R22") (pin "2") (pinfunction "2_2") (pintype "passive"))
      (node (ref "R25") (pin "2") (pinfunction "2_2") (pintype "passive"))
      (node (ref "R4") (pin "2") (pinfunction "2_2") (pintype "passive"))
      (node (ref "R7") (pin "2") (pinfunction "2_2") (pintype "passive"))
      (node (ref "U$3") (pin "A2") (pinfunction "1_A2") (pintype "bidirectional"))
    )
  )
)
